# Sheet_1_2020-07-29_17-52-00.net
KiCad netlist of a schematic drawn in Altium Designer
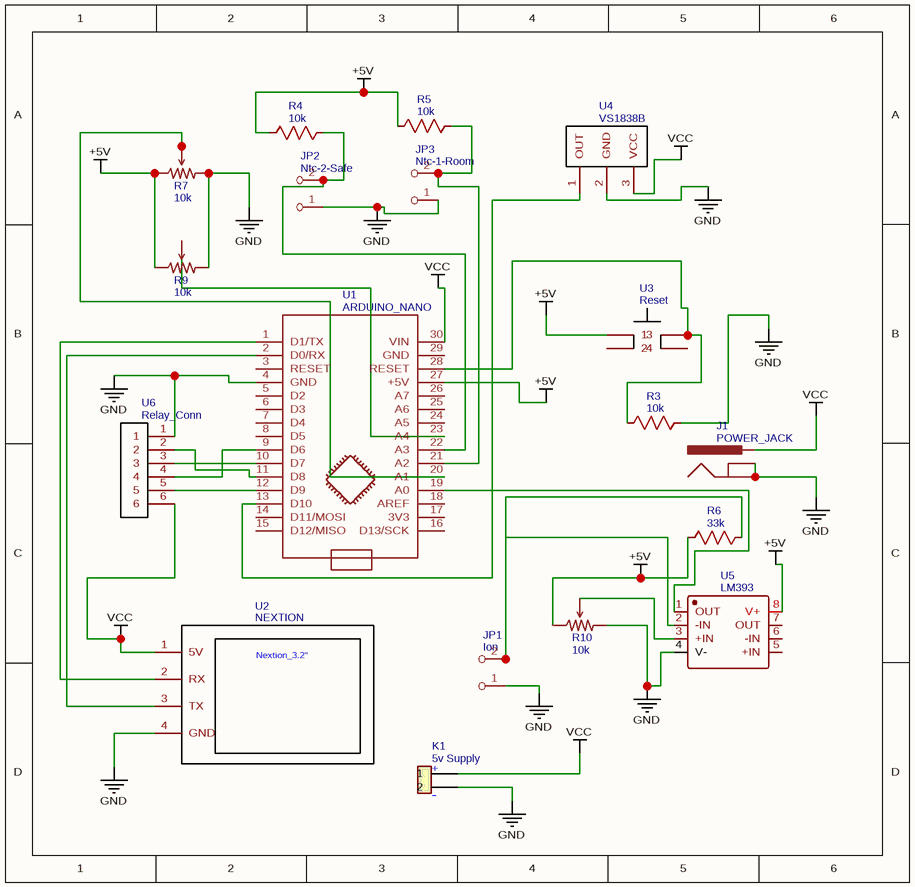
[diagram p0: Sheet_1_2020-07-29_17-52-00.schdoc]

(export (version "E")
  (design (tool "Eeschema 10.0.6"))
  (components
    (comp (ref "J1")
      (value "POWER_JACK")
      (fields (field (name "CONTRIBUTOR") "SparkFun"))
      (libsource (lib "altium-import") (part "root_0_POWER_JACK_"))
    )
    (comp (ref "JP1")
      (value "Ion")
      (fields (field (name "CONTRIBUTOR") "Adafruit"))
      (libsource (lib "altium-import") (part "root_2_Ion_"))
    )
    (comp (ref "JP2")
      (value "Ntc-2-Safe")
      (fields (field (name "CONTRIBUTOR") "Adafruit"))
      (libsource (lib "altium-import") (part "root_2_Ntc-2-Safe_"))
    )
    (comp (ref "JP3")
      (value "Ntc-1-Room")
      (fields (field (name "CONTRIBUTOR") "Adafruit"))
      (libsource (lib "altium-import") (part "root_2_Ntc-1-Room_"))
    )
    (comp (ref "K1")
      (value "5v Supply")
      (description "Header, 2-Pin")
      (libsource (lib "altium-import") (part "root_0_5v Supply_"))
    )
    (comp (ref "R3") (value "10k") (libsource (lib "") (part "root_0_10k__1")))
    (comp (ref "R4") (value "10k") (libsource (lib "") (part "root_0_10k__1")))
    (comp (ref "R5") (value "10k") (libsource (lib "") (part "root_0_10k__1")))
    (comp (ref "R6") (value "33k") (libsource (lib "altium-import") (part "root_0_33k_")))
    (comp (ref "R7")
      (value "10k")
      (fields (field (name "CONTRIBUTOR") "SparkFun"))
      (libsource (lib "altium-import") (part "root_0_10k_"))
    )
    (comp (ref "R9")
      (value "10k")
      (fields (field (name "CONTRIBUTOR") "SparkFun"))
      (libsource (lib "altium-import") (part "root_0_10k_"))
    )
    (comp (ref "R10")
      (value "10k")
      (fields (field (name "CONTRIBUTOR") "SparkFun"))
      (libsource (lib "altium-import") (part "root_0_10k_"))
    )
    (comp (ref "U1") (value "ARDUINO_NANO") (libsource (lib "altium-import") (part "root_0_ARDUINO_NANO_")))
    (comp (ref "U2")
      (value "NEXTION")
      (fields (field (name "BOM_MANUFACTURER PART") "NX3224T032") (field (name "CONTRIBUTOR") "rakowski.hub"))
      (libsource (lib "altium-import") (part "root_0_NEXTION_"))
    )
    (comp (ref "U3")
      (value "Reset")
      (fields (field (name "BOM_MANUFACTURER PART") "Pushbutton") (field (name "CONTRIBUTOR") "elnino"))
      (libsource (lib "altium-import") (part "root_0_Reset_"))
    )
    (comp (ref "U4")
      (value "VS1838B")
      (fields (field (name "CONTRIBUTOR") "franx411"))
      (libsource (lib "altium-import") (part "root_0_VS1838B_"))
    )
    (comp (ref "U5") (value "LM393") (libsource (lib "altium-import") (part "root_0_LM393_")))
    (comp (ref "U6")
      (value "Relay_Conn")
      (fields (field (name "CONTRIBUTOR") "M S Ali"))
      (libsource (lib "altium-import") (part "root_0_Relay_Conn_"))
    )
  )
  (nets
    (net (code "1") (name "+5V") (class "Default")
      (node (ref "R10") (pin "1") (pinfunction "CCW_1") (pintype "passive"))
      (node (ref "R4") (pin "1") (pinfunction "1_1") (pintype "passive"))
      (node (ref "R5") (pin "1") (pinfunction "1_1") (pintype "passive"))
      (node (ref "R6") (pin "1") (pinfunction "1_1") (pintype "passive"))
      (node (ref "R7") (pin "1") (pinfunction "CCW_1") (pintype "passive"))
      (node (ref "R9") (pin "1") (pinfunction "CCW_1") (pintype "passive"))
      (node (ref "U1") (pin "27") (pinfunction "+5V_27") (pintype "passive"))
      (node (ref "U3") (pin "1") (pinfunction "1_1") (pintype "passive"))
      (node (ref "U5") (pin "8") (pinfunction "V+_8") (pintype "passive"))
    )
    (net (code "2") (name "GND") (class "Default")
      (node (ref "J1") (pin "GND") (pinfunction "GND_GND") (pintype "passive"))
      (node (ref "J1") (pin "GNDBREAK") (pinfunction "GNDBREAK_GNDBREAK") (pintype "passive"))
      (node (ref "JP1") (pin "1") (pinfunction "1_1") (pintype "passive"))
      (node (ref "JP2") (pin "1") (pinfunction "1_1") (pintype "passive"))
      (node (ref "JP3") (pin "1") (pinfunction "1_1") (pintype "passive"))
      (node (ref "K1") (pin "2") (pinfunction "2_2") (pintype "passive"))
      (node (ref "R10") (pin "3") (pinfunction "CW_3") (pintype "passive"))
      (node (ref "R3") (pin "2") (pinfunction "2_2") (pintype "passive"))
      (node (ref "R7") (pin "3") (pinfunction "CW_3") (pintype "passive"))
      (node (ref "R9") (pin "3") (pinfunction "CW_3") (pintype "passive"))
      (node (ref "U1") (pin "4") (pinfunction "GND_4") (pintype "passive"))
      (node (ref "U2") (pin "4") (pinfunction "GND_4") (pintype "passive"))
      (node (ref "U4") (pin "2") (pinfunction "GND_2") (pintype "passive"))
      (node (ref "U5") (pin "4") (pinfunction "V-_4") (pintype "passive"))
      (node (ref "U6") (pin "1") (pinfunction "1_1") (pintype "passive"))
    )
    (net (code "3") (name "Net-(JP1-Pad2)") (class "Default")
      (node (ref "JP1") (pin "2") (pinfunction "2_2") (pintype "passive"))
      (node (ref "R6") (pin "2") (pinfunction "2_2") (pintype "passive"))
      (node (ref "U5") (pin "2") (pinfunction "-IN_2") (pintype "passive"))
    )
    (net (code "4") (name "Net-(R3-Pad1)") (class "Default")
      (node (ref "R3") (pin "1") (pinfunction "1_1") (pintype "passive"))
      (node (ref "U1") (pin "28") (pinfunction "RESET_28") (pintype "passive"))
      (node (ref "U3") (pin "3") (pinfunction "3_3") (pintype "passive"))
    )
    (net (code "5") (name "Net-(R7-WIPER)") (class "Default")
      (node (ref "R7") (pin "2") (pinfunction "WIPER_2") (pintype "passive"))
      (node (ref "U1") (pin "20") (pinfunction "A1_20") (pintype "passive"))
    )
    (net (code "6") (name "Net-(R9-WIPER)") (class "Default")
      (node (ref "R9") (pin "2") (pinfunction "WIPER_2") (pintype "passive"))
      (node (ref "U1") (pin "23") (pinfunction "A4_23") (pintype "passive"))
    )
    (net (code "7") (name "Net-(R10-WIPER)") (class "Default")
      (node (ref "R10") (pin "2") (pinfunction "WIPER_2") (pintype "passive"))
      (node (ref "U5") (pin "3") (pinfunction "+IN_3") (pintype "passive"))
    )
    (net (code "8") (name "Net-(U1-A0)") (class "Default")
      (node (ref "U1") (pin "19") (pinfunction "A0_19") (pintype "passive"))
      (node (ref "U5") (pin "1") (pinfunction "OUT_1") (pintype "passive"))
    )
    (net (code "9") (name "Net-(U1-A2)") (class "Default")
      (node (ref "JP3") (pin "2") (pinfunction "2_2") (pintype "passive"))
      (node (ref "R5") (pin "2") (pinfunction "2_2") (pintype "passive"))
      (node (ref "U1") (pin "21") (pinfunction "A2_21") (pintype "passive"))
    )
    (net (code "10") (name "Net-(U1-A3)") (class "Default")
      (node (ref "JP2") (pin "2") (pinfunction "2_2") (pintype "passive"))
      (node (ref "R4") (pin "2") (pinfunction "2_2") (pintype "passive"))
      (node (ref "U1") (pin "22") (pinfunction "A3_22") (pintype "passive"))
    )
    (net (code "11") (name "Net-(U1-D0{slash}RX)") (class "Default")
      (node (ref "U1") (pin "2") (pinfunction "D0/RX_2") (pintype "passive"))
      (node (ref "U2") (pin "3") (pinfunction "TX_3") (pintype "passive"))
    )
    (net (code "12") (name "Net-(U1-D1{slash}TX)") (class "Default")
      (node (ref "U1") (pin "1") (pinfunction "D1/TX_1") (pintype "passive"))
      (node (ref "U2") (pin "2") (pinfunction "RX_2") (pintype "passive"))
    )
    (net (code "13") (name "Net-(U1-D6)") (class "Default")
      (node (ref "U1") (pin "9") (pinfunction "D6_9") (pintype "passive"))
      (node (ref "U6") (pin "4") (pinfunction "4_4") (pintype "passive"))
    )
    (net (code "14") (name "Net-(U1-D7)") (class "Default")
      (node (ref "U1") (pin "10") (pinfunction "D7_10") (pintype "passive"))
      (node (ref "U6") (pin "3") (pinfunction "3_3") (pintype "passive"))
    )
    (net (code "15") (name "Net-(U1-D8)") (class "Default")
      (node (ref "U1") (pin "11") (pinfunction "D8_11") (pintype "passive"))
      (node (ref "U6") (pin "2") (pinfunction "2_2") (pintype "passive"))
    )
    (net (code "16") (name "Net-(U1-D9)") (class "Default")
      (node (ref "U1") (pin "12") (pinfunction "D9_12") (pintype "passive"))
      (node (ref "U6") (pin "5") (pinfunction "5_5") (pintype "passive"))
    )
    (net (code "17") (name "Net-(U1-D10)") (class "Default")
      (node (ref "U1") (pin "13") (pinfunction "D10_13") (pintype "passive"))
      (node (ref "U4") (pin "1") (pinfunction "OUT_1") (pintype "passive"))
    )
    (net (code "18") (name "VCC") (class "Default")
      (node (ref "J1") (pin "PWR") (pinfunction "PWR_PWR") (pintype "passive"))
      (node (ref "K1") (pin "1") (pinfunction "1_1") (pintype "passive"))
      (node (ref "U1") (pin "30") (pinfunction "VIN_30") (pintype "passive"))
      (node (ref "U2") (pin "1") (pinfunction "5V_1") (pintype "passive"))
      (node (ref "U4") (pin "3") (pinfunction "VCC_3") (pintype "passive"))
      (node (ref "U6") (pin "6") (pinfunction "6_6") (pintype "passive"))
    )
    (net (code "19") (name "unconnected-(U1-3V3-Pad17)") (class "Default")
      (node (ref "U1") (pin "17") (pinfunction "3V3_17") (pintype "passive"))
    )
    (net (code "20") (name "unconnected-(U1-A5-Pad24)") (class "Default")
      (node (ref "U1") (pin "24") (pinfunction "A5_24") (pintype "passive"))
    )
    (net (code "21") (name "unconnected-(U1-A6-Pad25)") (class "Default")
      (node (ref "U1") (pin "25") (pinfunction "A6_25") (pintype "passive"))
    )
    (net (code "22") (name "unconnected-(U1-A7-Pad26)") (class "Default")
      (node (ref "U1") (pin "26") (pinfunction "A7_26") (pintype "passive"))
    )
    (net (code "23") (name "unconnected-(U1-AREF-Pad18)") (class "Default")
      (node (ref "U1") (pin "18") (pinfunction "AREF_18") (pintype "passive"))
    )
    (net (code "24") (name "unconnected-(U1-D2-Pad5)") (class "Default")
      (node (ref "U1") (pin "5") (pinfunction "D2_5") (pintype "passive"))
    )
    (net (code "25") (name "unconnected-(U1-D3-Pad6)") (class "Default")
      (node (ref "U1") (pin "6") (pinfunction "D3_6") (pintype "passive"))
    )
    (net (code "26") (name "unconnected-(U1-D4-Pad7)") (class "Default")
      (node (ref "U1") (pin "7") (pinfunction "D4_7") (pintype "passive"))
    )
    (net (code "27") (name "unconnected-(U1-D5-Pad8)") (class "Default")
      (node (ref "U1") (pin "8") (pinfunction "D5_8") (pintype "passive"))
    )
    (net (code "28") (name "unconnected-(U1-D11{slash}MOSI-Pad14)") (class "Default")
      (node (ref "U1") (pin "14") (pinfunction "D11/MOSI_14") (pintype "passive"))
    )
    (net (code "29") (name "unconnected-(U1-D12{slash}MISO-Pad15)") (class "Default")
      (node (ref "U1") (pin "15") (pinfunction "D12/MISO_15") (pintype "passive"))
    )
    (net (code "30") (name "unconnected-(U1-D13{slash}SCK-Pad16)") (class "Default")
      (node (ref "U1") (pin "16") (pinfunction "D13/SCK_16") (pintype "passive"))
    )
    (net (code "31") (name "unconnected-(U1-GND-Pad29)") (class "Default")
      (node (ref "U1") (pin "29") (pinfunction "GND_29") (pintype "passive"))
    )
    (net (code "32") (name "unconnected-(U1-RESET-Pad3)") (class "Default")
      (node (ref "U1") (pin "3") (pinfunction "RESET_3") (pintype "passive"))
    )
    (net (code "33") (name "unconnected-(U3-Pad2)") (class "Default")
      (node (ref "U3") (pin "2") (pinfunction "2_2") (pintype "passive"))
    )
    (net (code "34") (name "unconnected-(U3-Pad4)") (class "Default")
      (node (ref "U3") (pin "4") (pinfunction "4_4") (pintype "passive"))
    )
    (net (code "35") (name "unconnected-(U5-+IN-Pad5)") (class "Default")
      (node (ref "U5") (pin "5") (pinfunction "+IN_5") (pintype "passive"))
    )
    (net (code "36") (name "unconnected-(U5--IN-Pad6)") (class "Default")
      (node (ref "U5") (pin "6") (pinfunction "-IN_6") (pintype "passive"))
    )
    (net (code "37") (name "unconnected-(U5-OUT-Pad7)") (class "Default")
      (node (ref "U5") (pin "7") (pinfunction "OUT_7") (pintype "passive"))
    )
  )
)
